# P12-Distancia_HC-SR04.net
KiCad netlist of a schematic drawn in EAGLE
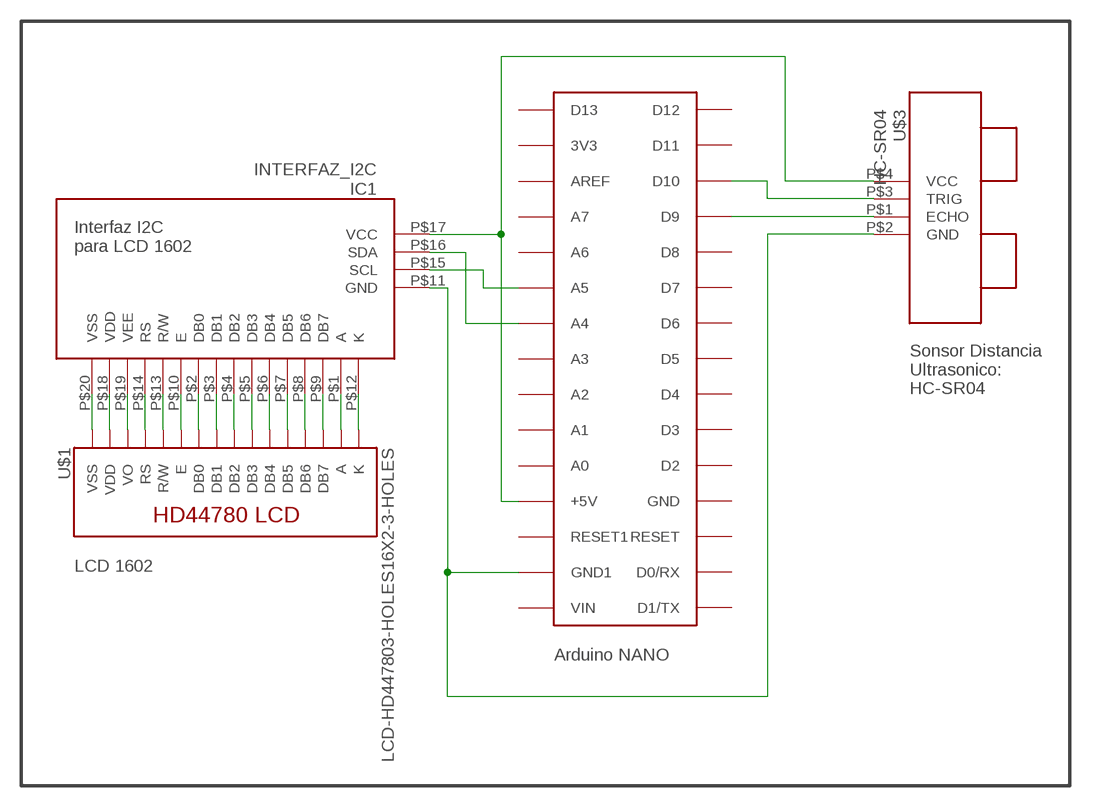
[diagram p0: schematic, sheet 1]

(export (version "E")
  (design (tool "Eeschema 10.0.6"))
  (components
    (comp (ref "IC1")
      (value "INTERFAZ_I2C")
      (footprint "eagle-import:NO_FOOTPRINT")
      (libsource (lib "eagle-import") (part "INTERFAZ_I2C"))
    )
    (comp (ref "U$1")
      (value "LCD-HD447803-HOLES16X2-3-HOLES")
      (footprint "eagle-import:LCD-16X2-3HOLES")
      (libsource (lib "eagle-import") (part "LCD-HD4478016X2-3-HOLES3-HOLES"))
    )
    (comp (ref "U$2")
      (value "ARDUINONANO")
      (footprint "eagle-import:PDIP-32")
      (libsource (lib "eagle-import") (part "ARDUINONANO"))
    )
    (comp (ref "U$3")
      (value "HC-SR04")
      (footprint "eagle-import:ASD")
      (libsource (lib "eagle-import") (part "HC-SR04"))
    )
  )
  (nets
    (net (code "1") (name "Net-(IC1-A)") (class "Default")
      (node (ref "IC1") (pin "P$1") (pinfunction "A_P$1") (pintype "bidirectional"))
      (node (ref "U$1") (pin "15") (pinfunction "A_15") (pintype "power_in"))
    )
    (net (code "2") (name "Net-(IC1-DB0)") (class "Default")
      (node (ref "IC1") (pin "P$2") (pinfunction "DB0_P$2") (pintype "bidirectional"))
      (node (ref "U$1") (pin "7") (pinfunction "DB0_7") (pintype "bidirectional"))
    )
    (net (code "3") (name "Net-(IC1-DB1)") (class "Default")
      (node (ref "IC1") (pin "P$3") (pinfunction "DB1_P$3") (pintype "bidirectional"))
      (node (ref "U$1") (pin "8") (pinfunction "DB1_8") (pintype "bidirectional"))
    )
    (net (code "4") (name "Net-(IC1-DB2)") (class "Default")
      (node (ref "IC1") (pin "P$4") (pinfunction "DB2_P$4") (pintype "bidirectional"))
      (node (ref "U$1") (pin "9") (pinfunction "DB2_9") (pintype "bidirectional"))
    )
    (net (code "5") (name "Net-(IC1-DB3)") (class "Default")
      (node (ref "IC1") (pin "P$5") (pinfunction "DB3_P$5") (pintype "bidirectional"))
      (node (ref "U$1") (pin "10") (pinfunction "DB3_10") (pintype "bidirectional"))
    )
    (net (code "6") (name "Net-(IC1-DB4)") (class "Default")
      (node (ref "IC1") (pin "P$6") (pinfunction "DB4_P$6") (pintype "bidirectional"))
      (node (ref "U$1") (pin "11") (pinfunction "DB4_11") (pintype "bidirectional"))
    )
    (net (code "7") (name "Net-(IC1-DB5)") (class "Default")
      (node (ref "IC1") (pin "P$7") (pinfunction "DB5_P$7") (pintype "bidirectional"))
      (node (ref "U$1") (pin "12") (pinfunction "DB5_12") (pintype "bidirectional"))
    )
    (net (code "8") (name "Net-(IC1-DB6)") (class "Default")
      (node (ref "IC1") (pin "P$8") (pinfunction "DB6_P$8") (pintype "bidirectional"))
      (node (ref "U$1") (pin "13") (pinfunction "DB6_13") (pintype "bidirectional"))
    )
    (net (code "9") (name "Net-(IC1-DB7)") (class "Default")
      (node (ref "IC1") (pin "P$9") (pinfunction "DB7_P$9") (pintype "bidirectional"))
      (node (ref "U$1") (pin "14") (pinfunction "DB7_14") (pintype "bidirectional"))
    )
    (net (code "10") (name "Net-(IC1-E)") (class "Default")
      (node (ref "IC1") (pin "P$10") (pinfunction "E_P$10") (pintype "bidirectional"))
      (node (ref "U$1") (pin "6") (pinfunction "E_6") (pintype "input"))
    )
    (net (code "11") (name "Net-(IC1-GND)") (class "Default")
      (node (ref "IC1") (pin "P$11") (pinfunction "GND_P$11") (pintype "bidirectional"))
      (node (ref "U$2") (pin "GND1") (pinfunction "GND1_GND1") (pintype "bidirectional"))
      (node (ref "U$3") (pin "P$2") (pinfunction "GND_P$2") (pintype "bidirectional"))
    )
    (net (code "12") (name "Net-(IC1-K)") (class "Default")
      (node (ref "IC1") (pin "P$12") (pinfunction "K_P$12") (pintype "bidirectional"))
      (node (ref "U$1") (pin "16") (pinfunction "K_16") (pintype "power_in"))
    )
    (net (code "13") (name "Net-(IC1-RS)") (class "Default")
      (node (ref "IC1") (pin "P$14") (pinfunction "RS_P$14") (pintype "bidirectional"))
      (node (ref "U$1") (pin "4") (pinfunction "RS_4") (pintype "input"))
    )
    (net (code "14") (name "Net-(IC1-R{slash}W)") (class "Default")
      (node (ref "IC1") (pin "P$13") (pinfunction "R/W_P$13") (pintype "bidirectional"))
      (node (ref "U$1") (pin "5") (pinfunction "R/W_5") (pintype "input"))
    )
    (net (code "15") (name "Net-(IC1-SCL)") (class "Default")
      (node (ref "IC1") (pin "P$15") (pinfunction "SCL_P$15") (pintype "bidirectional"))
      (node (ref "U$2") (pin "A5") (pinfunction "A5_A5") (pintype "bidirectional"))
    )
    (net (code "16") (name "Net-(IC1-SDA)") (class "Default")
      (node (ref "IC1") (pin "P$16") (pinfunction "SDA_P$16") (pintype "bidirectional"))
      (node (ref "U$2") (pin "A4") (pinfunction "A4_A4") (pintype "bidirectional"))
    )
    (net (code "17") (name "Net-(IC1-VCC)") (class "Default")
      (node (ref "IC1") (pin "P$17") (pinfunction "VCC_P$17") (pintype "bidirectional"))
      (node (ref "U$2") (pin "+5V") (pinfunction "+5V_+5V") (pintype "bidirectional"))
      (node (ref "U$3") (pin "P$4") (pinfunction "VCC_P$4") (pintype "bidirectional"))
    )
    (net (code "18") (name "Net-(IC1-VDD)") (class "Default")
      (node (ref "IC1") (pin "P$18") (pinfunction "VDD_P$18") (pintype "bidirectional"))
      (node (ref "U$1") (pin "2") (pinfunction "VDD_2") (pintype "power_in"))
    )
    (net (code "19") (name "Net-(IC1-VEE)") (class "Default")
      (node (ref "IC1") (pin "P$19") (pinfunction "VEE_P$19") (pintype "bidirectional"))
      (node (ref "U$1") (pin "3") (pinfunction "VO_3") (pintype "bidirectional"))
    )
    (net (code "20") (name "Net-(IC1-VSS)") (class "Default")
      (node (ref "IC1") (pin "P$20") (pinfunction "VSS_P$20") (pintype "bidirectional"))
      (node (ref "U$1") (pin "1") (pinfunction "VSS_1") (pintype "power_in"))
    )
    (net (code "21") (name "Net-(U$3-ECHO)") (class "Default")
      (node (ref "U$2") (pin "D9") (pinfunction "D9_D9") (pintype "bidirectional"))
      (node (ref "U$3") (pin "P$1") (pinfunction "ECHO_P$1") (pintype "bidirectional"))
    )
    (net (code "22") (name "Net-(U$3-TRIG)") (class "Default")
      (node (ref "U$2") (pin "D10") (pinfunction "D10_D10") (pintype "bidirectional"))
      (node (ref "U$3") (pin "P$3") (pinfunction "TRIG_P$3") (pintype "bidirectional"))
    )
    (net (code "23") (name "unconnected-(U$2-Pad3V3)") (class "Default")
      (node (ref "U$2") (pin "3V3") (pinfunction "3V3_3V3") (pintype "bidirectional"))
    )
    (net (code "24") (name "unconnected-(U$2-PadA0)") (class "Default")
      (node (ref "U$2") (pin "A0") (pinfunction "A0_A0") (pintype "bidirectional"))
    )
    (net (code "25") (name "unconnected-(U$2-PadA1)") (class "Default")
      (node (ref "U$2") (pin "A1") (pinfunction "A1_A1") (pintype "bidirectional"))
    )
    (net (code "26") (name "unconnected-(U$2-PadA2)") (class "Default")
      (node (ref "U$2") (pin "A2") (pinfunction "A2_A2") (pintype "bidirectional"))
    )
    (net (code "27") (name "unconnected-(U$2-PadA3)") (class "Default")
      (node (ref "U$2") (pin "A3") (pinfunction "A3_A3") (pintype "bidirectional"))
    )
    (net (code "28") (name "unconnected-(U$2-PadA6)") (class "Default")
      (node (ref "U$2") (pin "A6") (pinfunction "A6_A6") (pintype "bidirectional"))
    )
    (net (code "29") (name "unconnected-(U$2-PadA7)") (class "Default")
      (node (ref "U$2") (pin "A7") (pinfunction "A7_A7") (pintype "bidirectional"))
    )
    (net (code "30") (name "unconnected-(U$2-PadAREF)") (class "Default")
      (node (ref "U$2") (pin "AREF") (pinfunction "AREF_AREF") (pintype "bidirectional"))
    )
    (net (code "31") (name "unconnected-(U$2-PadD0{slash}RX)") (class "Default")
      (node (ref "U$2") (pin "D0/RX") (pinfunction "D0/RX_D0/RX") (pintype "bidirectional"))
    )
    (net (code "32") (name "unconnected-(U$2-PadD1{slash}TX)") (class "Default")
      (node (ref "U$2") (pin "D1/TX") (pinfunction "D1/TX_D1/TX") (pintype "bidirectional"))
    )
    (net (code "33") (name "unconnected-(U$2-PadD2)") (class "Default")
      (node (ref "U$2") (pin "D2") (pinfunction "D2_D2") (pintype "bidirectional"))
    )
    (net (code "34") (name "unconnected-(U$2-PadD3)") (class "Default")
      (node (ref "U$2") (pin "D3") (pinfunction "D3_D3") (pintype "bidirectional"))
    )
    (net (code "35") (name "unconnected-(U$2-PadD4)") (class "Default")
      (node (ref "U$2") (pin "D4") (pinfunction "D4_D4") (pintype "bidirectional"))
    )
    (net (code "36") (name "unconnected-(U$2-PadD5)") (class "Default")
      (node (ref "U$2") (pin "D5") (pinfunction "D5_D5") (pintype "bidirectional"))
    )
    (net (code "37") (name "unconnected-(U$2-PadD6)") (class "Default")
      (node (ref "U$2") (pin "D6") (pinfunction "D6_D6") (pintype "bidirectional"))
    )
    (net (code "38") (name "unconnected-(U$2-PadD7)") (class "Default")
      (node (ref "U$2") (pin "D7") (pinfunction "D7_D7") (pintype "bidirectional"))
    )
    (net (code "39") (name "unconnected-(U$2-PadD8)") (class "Default")
      (node (ref "U$2") (pin "D8") (pinfunction "D8_D8") (pintype "bidirectional"))
    )
    (net (code "40") (name "unconnected-(U$2-PadD11)") (class "Default")
      (node (ref "U$2") (pin "D11") (pinfunction "D11_D11") (pintype "bidirectional"))
    )
    (net (code "41") (name "unconnected-(U$2-PadD12)") (class "Default")
      (node (ref "U$2") (pin "D12") (pinfunction "D12_D12") (pintype "bidirectional"))
    )
    (net (code "42") (name "unconnected-(U$2-PadD13)") (class "Default")
      (node (ref "U$2") (pin "D13") (pinfunction "D13_D13") (pintype "bidirectional"))
    )
    (net (code "43") (name "unconnected-(U$2-PadGND)") (class "Default")
      (node (ref "U$2") (pin "GND") (pinfunction "GND_GND") (pintype "bidirectional"))
    )
    (net (code "44") (name "unconnected-(U$2-PadRESET)") (class "Default")
      (node (ref "U$2") (pin "RESET") (pinfunction "RESET_RESET") (pintype "bidirectional"))
    )
    (net (code "45") (name "unconnected-(U$2-PadRESET1)") (class "Default")
      (node (ref "U$2") (pin "RESET1") (pinfunction "RESET1_RESET1") (pintype "bidirectional"))
    )
    (net (code "46") (name "unconnected-(U$2-PadVIN)") (class "Default")
      (node (ref "U$2") (pin "VIN") (pinfunction "VIN_VIN") (pintype "bidirectional"))
    )
  )
)
